# Power.net
KiCad netlist of a schematic drawn in Altium Designer
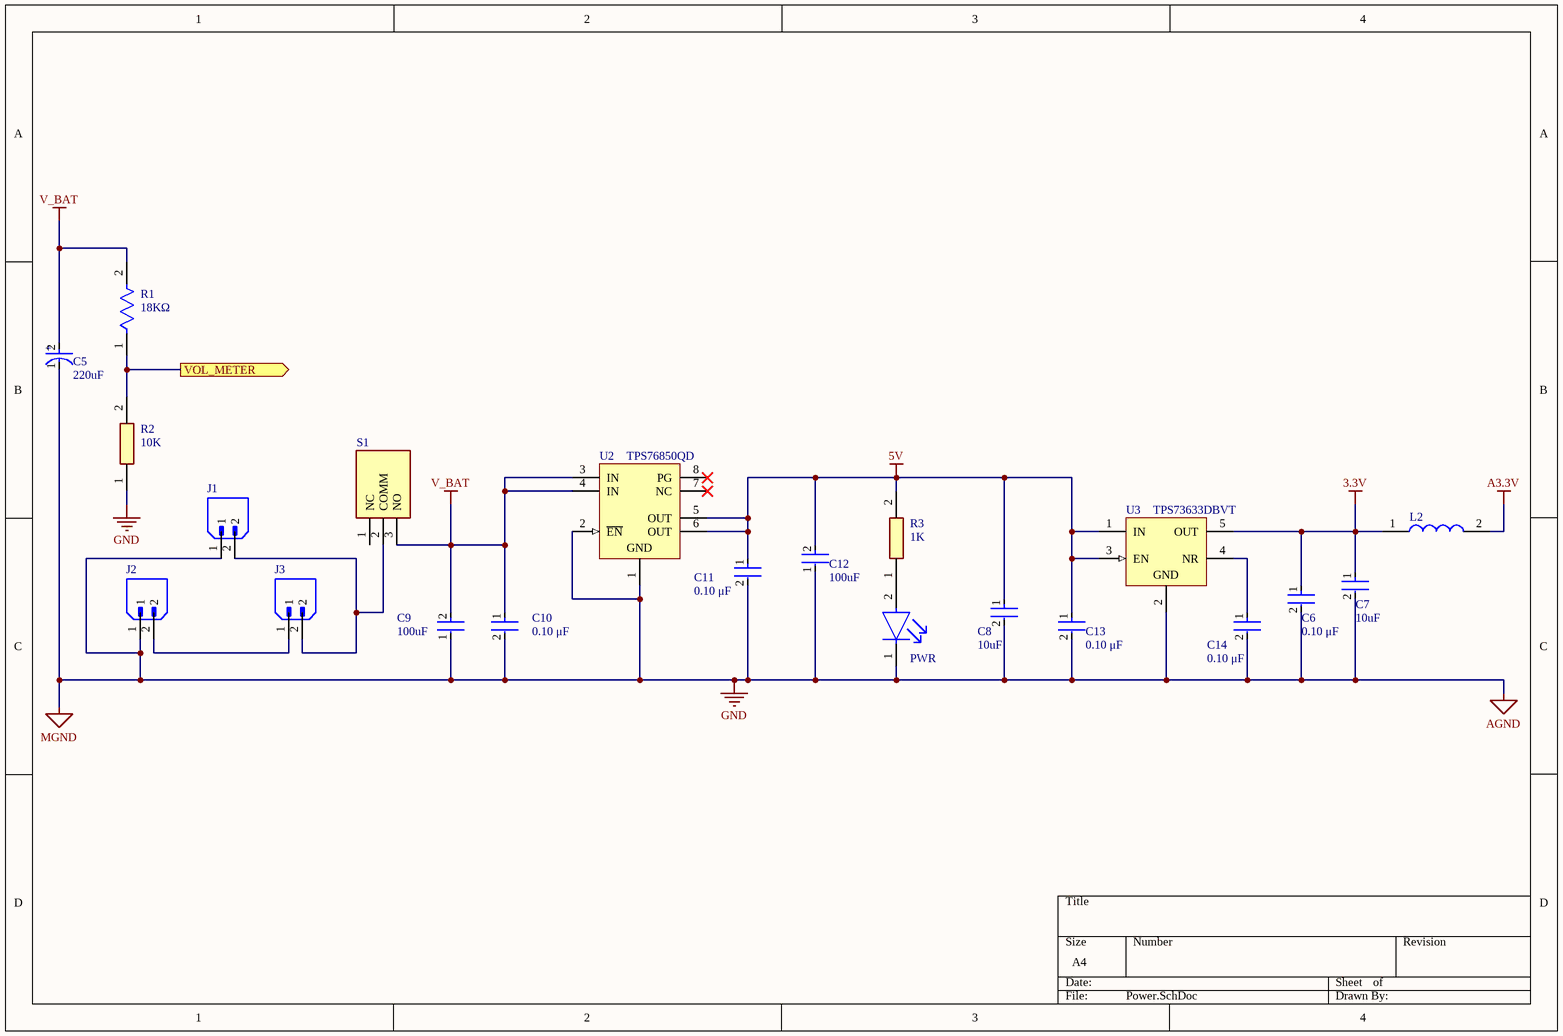
[diagram p0: Power.SchDoc]

(export (version "E")
  (design (tool "Eeschema 10.0.6"))
  (components
    (comp (ref "C5")
      (value "EEEFT1H221AP")
      (footprint "FP-FTF-MFG")
      (description "CAP ALUM 220UF 20% 50V SMD")
      (fields
        (field (name "CAPACITANCE") "220uF")
        (field (name "TOLERANCE") "20%")
        (field (name "VOLTAGE") "50V")
      )
      (libsource (lib "Altium Content Vault") (part "203bc49f2ac43e59fd269a8c329ed05"))
    )
    (comp (ref "C6")
      (value "0.10 μF")
      (footprint "FP-C1206C-EB-MFG")
      (description "CAP CER 0.1UF 100V X7R 1206")
      (fields
        (field (name "TOLERANCE") "0.1")
        (field (name "OCTOPART") "https://octopart.com/c1206c104k1ractu-kemet-89521")
      )
      (libsource (lib "Altium Content Vault") (part "b4654b650e69147ec39a6b967a45e02"))
    )
    (comp (ref "C7")
      (value "GRM21BR61C106KE15L")
      (footprint "FP-GRM21B-0_1-IPC_C")
      (description "Chip Multilayer Ceramic Capacitors for General Purpose, 0805, 10uF, X5R, 15%, 10%, 16V")
      (fields
        (field (name "TOLERANCE") "10%")
        (field (name "VOLTAGE") "16V")
        (field (name "CAPACITANCE") "10uF")
      )
      (libsource (lib "Altium Content Vault") (part "b4654b650e69147ec39a6b967a45e02"))
    )
    (comp (ref "C8")
      (value "GRM21BR61C106KE15L")
      (footprint "FP-GRM21B-0_1-IPC_C")
      (description "Chip Multilayer Ceramic Capacitors for General Purpose, 0805, 10uF, X5R, 15%, 10%, 16V")
      (fields
        (field (name "TOLERANCE") "10%")
        (field (name "VOLTAGE") "16V")
        (field (name "CAPACITANCE") "10uF")
      )
      (libsource (lib "Altium Content Vault") (part "b4654b650e69147ec39a6b967a45e02"))
    )
    (comp (ref "C9")
      (value "100uF")
      (footprint "FP-EMK325A-M-MFG")
      (description "CAP CER 100UF 16V X5R 1210")
      (fields
        (field (name "OCTOPART") "https://octopart.com/emk325abj107mm-t-taiyo+yuden-20815747")
        (field (name "MANUFACTURER PART NUMBER") "EMK325ABJ107MM-T")
      )
      (libsource (lib "Altium Content Vault") (part "f23184f103b6ebe33a8c269c53dcba6"))
    )
    (comp (ref "C10")
      (value "0.10 μF")
      (footprint "FP-C1206C-EB-MFG")
      (description "CAP CER 0.1UF 100V X7R 1206")
      (fields
        (field (name "TOLERANCE") "0.1")
        (field (name "OCTOPART") "https://octopart.com/c1206c104k1ractu-kemet-89521")
      )
      (libsource (lib "Altium Content Vault") (part "b4654b650e69147ec39a6b967a45e02"))
    )
    (comp (ref "C11")
      (value "0.10 μF")
      (footprint "FP-C1206C-EB-MFG")
      (description "CAP CER 0.1UF 100V X7R 1206")
      (fields
        (field (name "TOLERANCE") "0.1")
        (field (name "OCTOPART") "https://octopart.com/c1206c104k1ractu-kemet-89521")
      )
      (libsource (lib "Altium Content Vault") (part "b4654b650e69147ec39a6b967a45e02"))
    )
    (comp (ref "C12")
      (value "100uF")
      (footprint "FP-EMK325A-M-MFG")
      (description "CAP CER 100UF 16V X5R 1210")
      (fields
        (field (name "OCTOPART") "https://octopart.com/emk325abj107mm-t-taiyo+yuden-20815747")
        (field (name "MANUFACTURER PART NUMBER") "EMK325ABJ107MM-T")
      )
      (libsource (lib "Altium Content Vault") (part "f23184f103b6ebe33a8c269c53dcba6"))
    )
    (comp (ref "C13")
      (value "0.10 μF")
      (footprint "FP-C1206C-EB-MFG")
      (description "CAP CER 0.1UF 100V X7R 1206")
      (fields
        (field (name "TOLERANCE") "0.1")
        (field (name "OCTOPART") "https://octopart.com/c1206c104k1ractu-kemet-89521")
      )
      (libsource (lib "Altium Content Vault") (part "b4654b650e69147ec39a6b967a45e02"))
    )
    (comp (ref "C14")
      (value "0.10 μF")
      (footprint "FP-C1206C-EB-MFG")
      (description "CAP CER 0.1UF 100V X7R 1206")
      (fields
        (field (name "TOLERANCE") "0.1")
        (field (name "OCTOPART") "https://octopart.com/c1206c104k1ractu-kemet-89521")
      )
      (libsource (lib "Altium Content Vault") (part "b4654b650e69147ec39a6b967a45e02"))
    )
    (comp (ref "J1")
      (value "B2B-XH-A(LF)(SN)")
      (footprint "JST_B2B-XH-A(LF)(SN)")
      (description "Connector Header Through Hole 2 position 0.098 (2.50mm)")
      (fields (field (name "MF") "JST Sales America Inc."))
      (libsource (lib "B2B-XH-A_LF__SN_") (part "B2B-XH-A(LF)(SN)"))
    )
    (comp (ref "J2")
      (value "B2B-XH-A(LF)(SN)")
      (footprint "JST_B2B-XH-A(LF)(SN)")
      (description "Connector Header Through Hole 2 position 0.098 (2.50mm)")
      (fields (field (name "MF") "JST Sales America Inc."))
      (libsource (lib "B2B-XH-A_LF__SN_") (part "B2B-XH-A(LF)(SN)"))
    )
    (comp (ref "J3")
      (value "B2B-XH-A(LF)(SN)")
      (footprint "JST_B2B-XH-A(LF)(SN)")
      (description "Connector Header Through Hole 2 position 0.098 (2.50mm)")
      (fields (field (name "MF") "JST Sales America Inc."))
      (libsource (lib "B2B-XH-A_LF__SN_") (part "B2B-XH-A(LF)(SN)"))
    )
    (comp (ref "L2")
      (value "LBR2012T100K")
      (footprint "SamacSys:INDC2012X145N")
      (description "Inductor")
      (fields (field (name "MOUSER PART NUMBER") "963-LBR2012T100K"))
      (libsource (lib "*") (part "LBR2012T100K"))
    )
    (comp (ref "PWR")
      (value "HSMS-C150")
      (footprint "FP-HSMS-C150-MFG")
      (description "LED RED DIFFUSED CHIP SMD")
      (libsource (lib "Altium Content Vault") (part "8706943c75ba83719d021d2fdc84c58"))
    )
    (comp (ref "R1")
      (value "18KΩ")
      (footprint "FP-CRGCQ2010-IPC_C")
      (description "CRGCQ2010 18KΩ 0.75W ±100ppm/°C 1% 200V")
      (fields
        (field (name "MANUFACTURER PART NUMBER") "CRGCQ2010F18K")
        (field (name "MANUFACTURER") "TE Connectivity")
      )
      (libsource (lib "Altium Content Vault") (part "1029c3af85768c4190bb7ad29bc67b5"))
    )
    (comp (ref "R2")
      (value "10K")
      (footprint "SamacSys:ERJP06D1000V")
      (description "Resistor")
      (fields (field (name "MANUFACTURER_PART_NUMBER") "ERJ-P06D1002V"))
      (libsource (lib "*") (part "ERJ-P06D1002V"))
    )
    (comp (ref "R3")
      (value "1K")
      (footprint "SamacSys:RESC2013X65N")
      (description "Resistor")
      (fields
        (field (name "MANUFACTURER_PART_NUMBER") "0805W8F1001T5E")
        (field (name "MOUSER PART NUMBER") "303-0805W8F1001T5E")
      )
      (libsource (lib "*") (part "0805W8F1001T5E"))
    )
    (comp (ref "S1")
      (value "EG1218")
      (footprint "SamacSys:EG1218")
      (description "Switch")
      (fields (field (name "MOUSER PART NUMBER") "612-EG1218"))
      (libsource (lib "*") (part "EG1218"))
    )
    (comp (ref "U2")
      (value "TPS76850QD")
      (footprint "D0008A_L")
      (fields (field (name "MANUFACTURER") "Texas Instruments"))
      (libsource (lib "Altium Content Vault") (part "TI-TPS7XXXXD8_A"))
    )
    (comp (ref "U3")
      (value "TPS73633DBVT")
      (footprint "DBV0005A_M")
      (fields (field (name "MANUFACTURER") "Texas Instruments"))
      (libsource (lib "Altium Content Vault") (part "TI-TPS79NXX-YYSOT5"))
    )
  )
  (nets
    (net (code "1") (name "/VOL_METER") (class "Default")
      (node (ref "R1") (pin "1") (pinfunction "1_1") (pintype "passive"))
      (node (ref "R2") (pin "2") (pinfunction "2_2") (pintype "passive"))
    )
    (net (code "2") (name "3.3V") (class "Default")
      (node (ref "C6") (pin "1") (pinfunction "1_1") (pintype "passive"))
      (node (ref "C7") (pin "1") (pinfunction "1_1") (pintype "passive"))
      (node (ref "L2") (pin "1") (pinfunction "1_1") (pintype "passive"))
      (node (ref "U3") (pin "5") (pinfunction "OUT_5") (pintype "power_in"))
    )
    (net (code "3") (name "5V") (class "Default")
      (node (ref "C11") (pin "1") (pinfunction "1_1") (pintype "passive"))
      (node (ref "C12") (pin "2") (pinfunction "2_2") (pintype "passive"))
      (node (ref "C13") (pin "1") (pinfunction "1_1") (pintype "passive"))
      (node (ref "C8") (pin "1") (pinfunction "1_1") (pintype "passive"))
      (node (ref "R3") (pin "2") (pinfunction "2_2") (pintype "passive"))
      (node (ref "U2") (pin "5") (pinfunction "OUT_5") (pintype "power_in"))
      (node (ref "U2") (pin "6") (pinfunction "OUT_6") (pintype "power_in"))
      (node (ref "U3") (pin "1") (pinfunction "IN_1") (pintype "power_in"))
      (node (ref "U3") (pin "3") (pinfunction "EN_3") (pintype "input"))
    )
    (net (code "4") (name "A3.3V") (class "Default")
      (node (ref "L2") (pin "2") (pinfunction "2_2") (pintype "passive"))
    )
    (net (code "5") (name "AGND") (class "Default")
      (node (ref "C10") (pin "2") (pinfunction "2_2") (pintype "passive"))
      (node (ref "C11") (pin "2") (pinfunction "2_2") (pintype "passive"))
      (node (ref "C12") (pin "1") (pinfunction "1_1") (pintype "passive"))
      (node (ref "C13") (pin "2") (pinfunction "2_2") (pintype "passive"))
      (node (ref "C14") (pin "2") (pinfunction "2_2") (pintype "passive"))
      (node (ref "C5") (pin "1") (pinfunction "C_1") (pintype "passive"))
      (node (ref "C6") (pin "2") (pinfunction "2_2") (pintype "passive"))
      (node (ref "C7") (pin "2") (pinfunction "2_2") (pintype "passive"))
      (node (ref "C8") (pin "2") (pinfunction "2_2") (pintype "passive"))
      (node (ref "C9") (pin "1") (pinfunction "1_1") (pintype "passive"))
      (node (ref "J1") (pin "1") (pinfunction "1_1") (pintype "passive"))
      (node (ref "J2") (pin "1") (pinfunction "1_1") (pintype "passive"))
      (node (ref "PWR") (pin "1") (pinfunction "C_1") (pintype "passive"))
      (node (ref "R2") (pin "1") (pinfunction "1_1") (pintype "passive"))
      (node (ref "U2") (pin "1") (pinfunction "GND_1") (pintype "power_in"))
      (node (ref "U2") (pin "2") (pinfunction "~{EN}_2") (pintype "input"))
      (node (ref "U3") (pin "2") (pinfunction "GND_2") (pintype "power_in"))
    )
    (net (code "6") (name "Net-(J2-Pad2)") (class "Default")
      (node (ref "J2") (pin "2") (pinfunction "2_2") (pintype "passive"))
      (node (ref "J3") (pin "1") (pinfunction "1_1") (pintype "passive"))
    )
    (net (code "7") (name "Net-(PWR-A)") (class "Default")
      (node (ref "PWR") (pin "2") (pinfunction "A_2") (pintype "passive"))
      (node (ref "R3") (pin "1") (pinfunction "1_1") (pintype "passive"))
    )
    (net (code "8") (name "Net-(S1-COMM)") (class "Default")
      (node (ref "J1") (pin "2") (pinfunction "2_2") (pintype "passive"))
      (node (ref "J3") (pin "2") (pinfunction "2_2") (pintype "passive"))
      (node (ref "S1") (pin "2") (pinfunction "COMM_2") (pintype "passive"))
    )
    (net (code "9") (name "Net-(U3-NR)") (class "Default")
      (node (ref "C14") (pin "1") (pinfunction "1_1") (pintype "passive"))
      (node (ref "U3") (pin "4") (pinfunction "NR_4") (pintype "passive"))
    )
    (net (code "10") (name "V_BAT") (class "Default")
      (node (ref "C10") (pin "1") (pinfunction "1_1") (pintype "passive"))
      (node (ref "C5") (pin "2") (pinfunction "A_2") (pintype "passive"))
      (node (ref "C9") (pin "2") (pinfunction "2_2") (pintype "passive"))
      (node (ref "R1") (pin "2") (pinfunction "2_2") (pintype "passive"))
      (node (ref "S1") (pin "3") (pinfunction "NO_3") (pintype "passive"))
      (node (ref "U2") (pin "3") (pinfunction "IN_3") (pintype "power_in"))
      (node (ref "U2") (pin "4") (pinfunction "IN_4") (pintype "power_in"))
    )
    (net (code "11") (name "unconnected-(S1-NC-Pad1)") (class "Default")
      (node (ref "S1") (pin "1") (pinfunction "NC_1") (pintype "passive"))
    )
    (net (code "12") (name "unconnected-(U2-NC-Pad7)") (class "Default")
      (node (ref "U2") (pin "7") (pinfunction "NC_7") (pintype "passive+no_connect"))
    )
    (net (code "13") (name "unconnected-(U2-PG-Pad8)") (class "Default")
      (node (ref "U2") (pin "8") (pinfunction "PG_8") (pintype "tri_state+no_connect"))
    )
  )
)
